# Connectors.net
KiCad netlist of a schematic drawn in Altium Designer
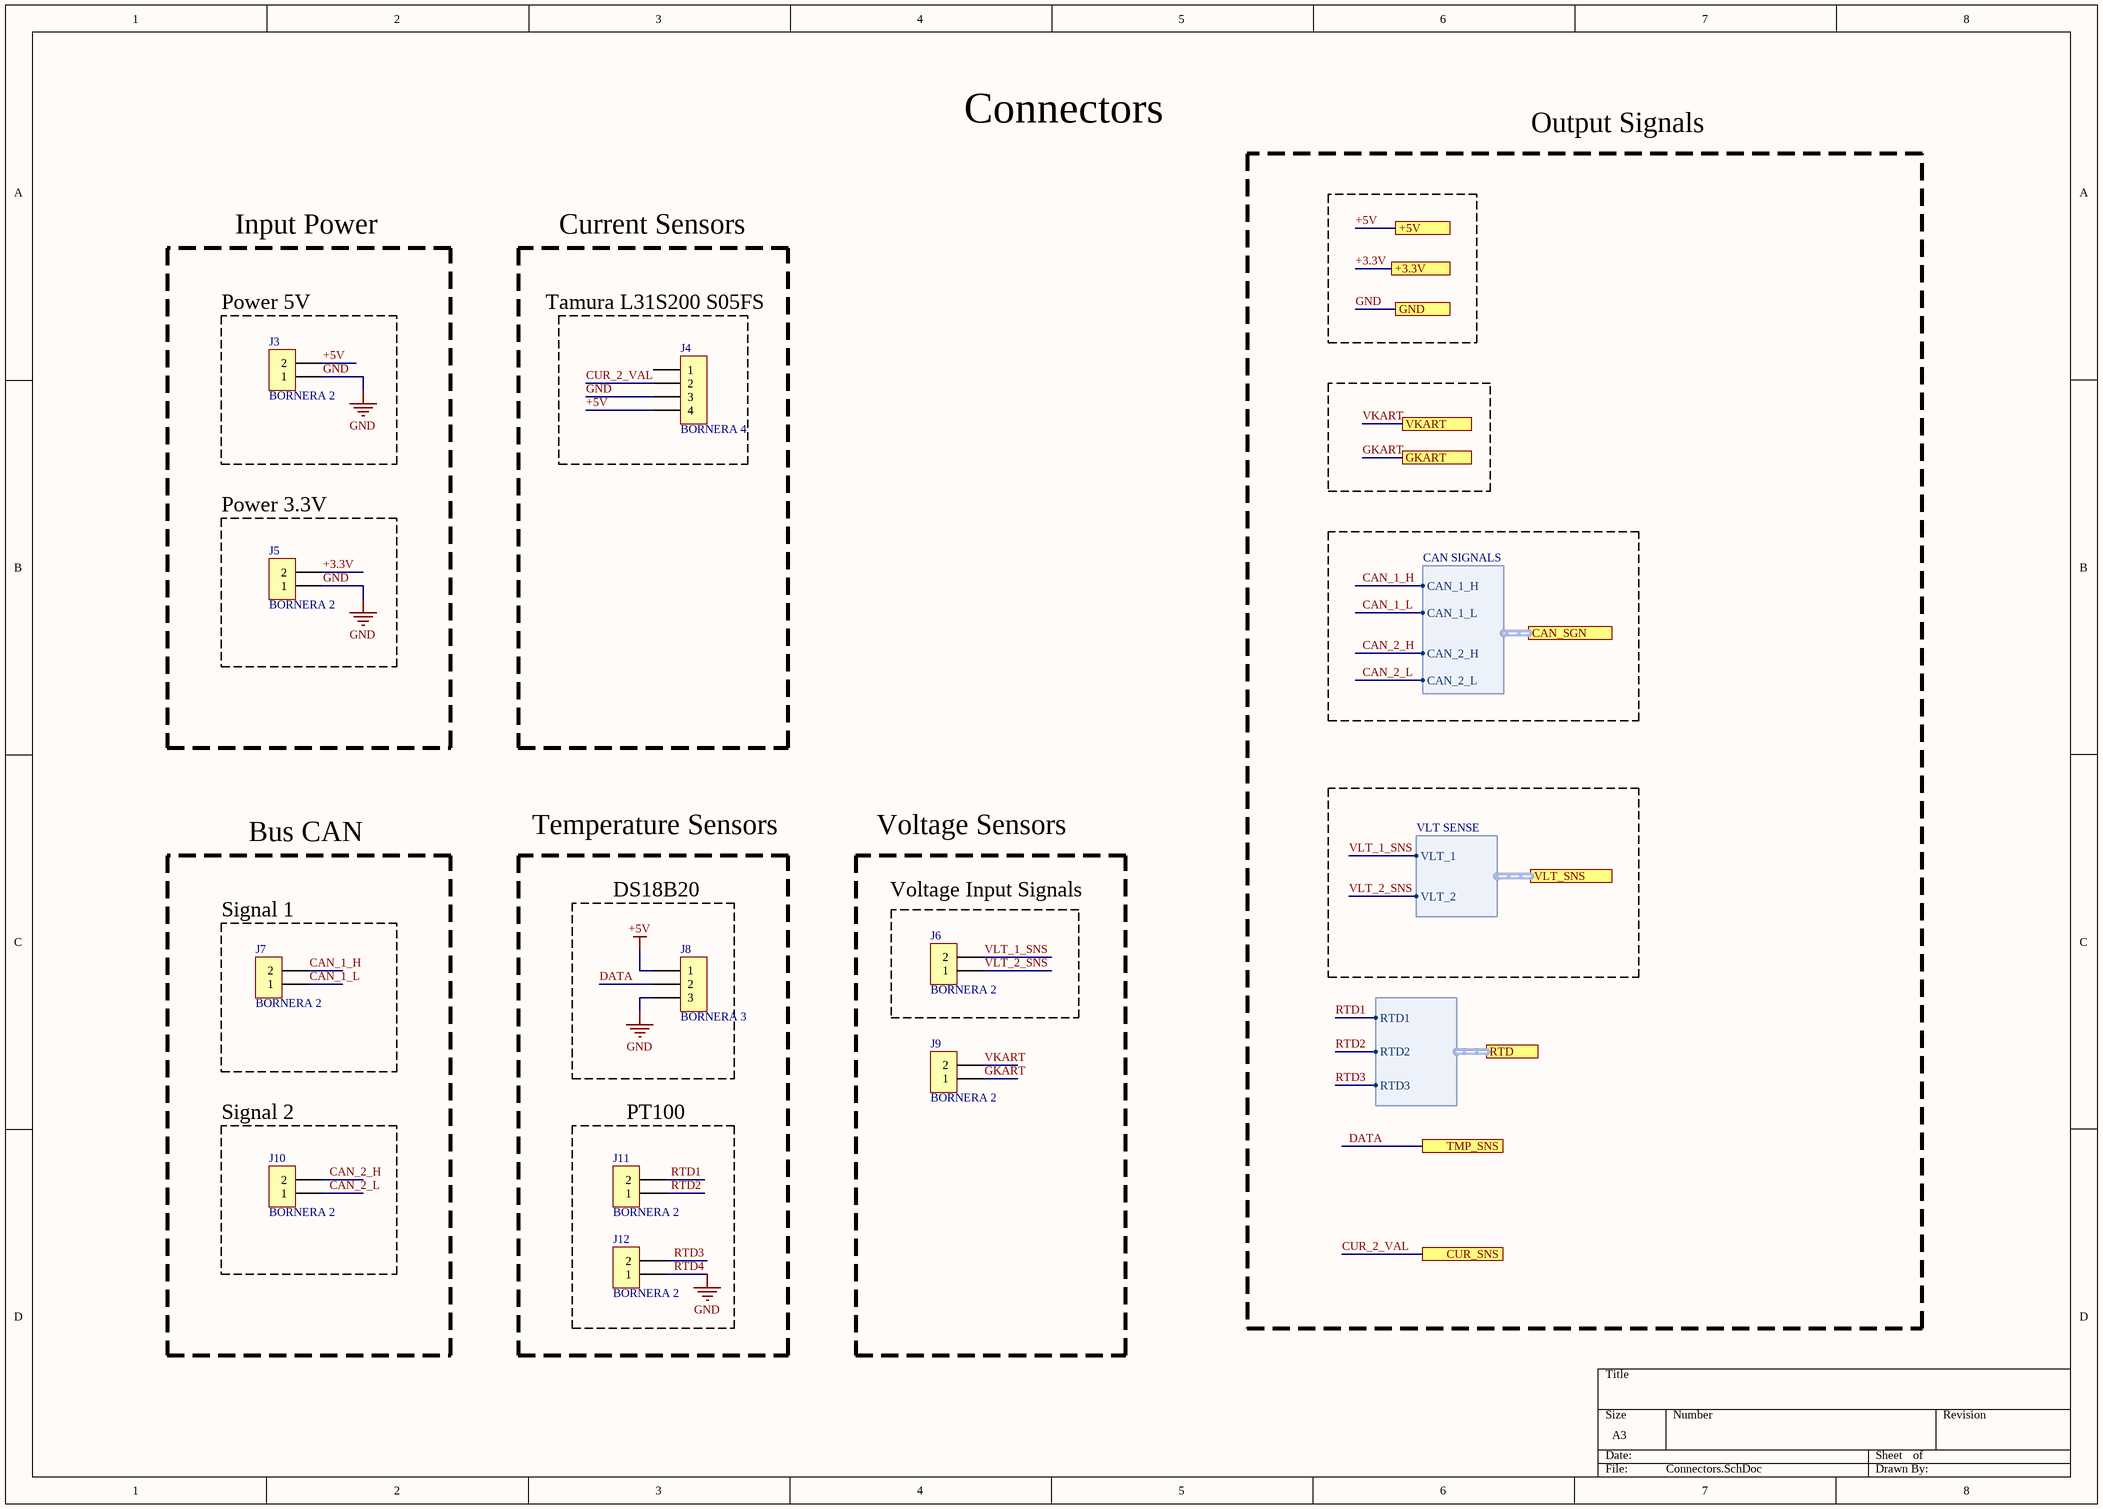
[diagram p0: Connectors.SchDoc]

(export (version "E")
  (design (tool "Eeschema 10.0.6"))
  (components
    (comp (ref "J3")
      (value "BORNERA 2")
      (footprint "BORNERA2")
      (libsource (lib "LIBEBAL") (part "BORNERA 2"))
    )
    (comp (ref "J4")
      (value "BORNERA 4")
      (footprint "BORNERA4")
      (libsource (lib "LIBEBAL") (part "BORNERA 4"))
    )
    (comp (ref "J5")
      (value "BORNERA 2")
      (footprint "BORNERA2")
      (libsource (lib "LIBEBAL") (part "BORNERA 2"))
    )
    (comp (ref "J6")
      (value "BORNERA 2")
      (footprint "BORNERA2")
      (libsource (lib "LIBEBAL") (part "BORNERA 2"))
    )
    (comp (ref "J7")
      (value "BORNERA 2")
      (footprint "BORNERA2")
      (libsource (lib "LIBEBAL") (part "BORNERA 2"))
    )
    (comp (ref "J8")
      (value "BORNERA 3")
      (footprint "BORNERA3")
      (libsource (lib "LIBEBAL") (part "BORNERA 3"))
    )
    (comp (ref "J9")
      (value "BORNERA 2")
      (footprint "BORNERA2")
      (libsource (lib "LIBEBAL") (part "BORNERA 2"))
    )
    (comp (ref "J10")
      (value "BORNERA 2")
      (footprint "BORNERA2")
      (libsource (lib "LIBEBAL") (part "BORNERA 2"))
    )
    (comp (ref "J11")
      (value "BORNERA 2")
      (footprint "BORNERA2")
      (libsource (lib "LIBEBAL") (part "BORNERA 2"))
    )
    (comp (ref "J12")
      (value "BORNERA 2")
      (footprint "BORNERA2")
      (libsource (lib "LIBEBAL") (part "BORNERA 2"))
    )
  )
  (nets
    (net (code "5") (name "+5V") (class "Default")
      (node (ref "J3") (pin "2") (pinfunction "2_2") (pintype "passive"))
      (node (ref "J4") (pin "4") (pinfunction "4_4") (pintype "passive"))
      (node (ref "J8") (pin "1") (pinfunction "1_1") (pintype "passive"))
    )
    (net (code "6") (name "/+3.3V") (class "Default")
      (node (ref "J5") (pin "2") (pinfunction "2_2") (pintype "passive"))
    )
    (net (code "7") (name "/CAN_1_H") (class "Default")
      (node (ref "J7") (pin "2") (pinfunction "2_2") (pintype "passive"))
    )
    (net (code "8") (name "/CAN_1_L") (class "Default")
      (node (ref "J7") (pin "1") (pinfunction "1_1") (pintype "passive"))
    )
    (net (code "9") (name "/CAN_2_H") (class "Default")
      (node (ref "J10") (pin "2") (pinfunction "2_2") (pintype "passive"))
    )
    (net (code "10") (name "/CAN_2_L") (class "Default")
      (node (ref "J10") (pin "1") (pinfunction "1_1") (pintype "passive"))
    )
    (net (code "11") (name "/CUR_2_VAL") (class "Default")
      (node (ref "J4") (pin "2") (pinfunction "2_2") (pintype "passive"))
    )
    (net (code "12") (name "/DATA") (class "Default")
      (node (ref "J8") (pin "2") (pinfunction "2_2") (pintype "passive"))
    )
    (net (code "13") (name "/GKART") (class "Default")
      (node (ref "J9") (pin "1") (pinfunction "1_1") (pintype "passive"))
    )
    (net (code "14") (name "/RTD1") (class "Default")
      (node (ref "J11") (pin "2") (pinfunction "2_2") (pintype "passive"))
    )
    (net (code "15") (name "/RTD2") (class "Default")
      (node (ref "J11") (pin "1") (pinfunction "1_1") (pintype "passive"))
    )
    (net (code "16") (name "/RTD3") (class "Default")
      (node (ref "J12") (pin "2") (pinfunction "2_2") (pintype "passive"))
    )
    (net (code "17") (name "/VKART") (class "Default")
      (node (ref "J9") (pin "2") (pinfunction "2_2") (pintype "passive"))
    )
    (net (code "18") (name "/VLT_1_SNS") (class "Default")
      (node (ref "J6") (pin "2") (pinfunction "2_2") (pintype "passive"))
    )
    (net (code "19") (name "/VLT_2_SNS") (class "Default")
      (node (ref "J6") (pin "1") (pinfunction "1_1") (pintype "passive"))
    )
    (net (code "23") (name "GND") (class "Default")
      (node (ref "J12") (pin "1") (pinfunction "1_1") (pintype "passive"))
      (node (ref "J3") (pin "1") (pinfunction "1_1") (pintype "passive"))
      (node (ref "J4") (pin "3") (pinfunction "3_3") (pintype "passive"))
      (node (ref "J5") (pin "1") (pinfunction "1_1") (pintype "passive"))
      (node (ref "J8") (pin "3") (pinfunction "3_3") (pintype "passive"))
    )
    (net (code "24") (name "unconnected-(J4-Pad1)") (class "Default")
      (node (ref "J4") (pin "1") (pinfunction "1_1") (pintype "passive"))
    )
  )
)
